# design_1.net
KiCad netlist of a schematic drawn in Altium Designer
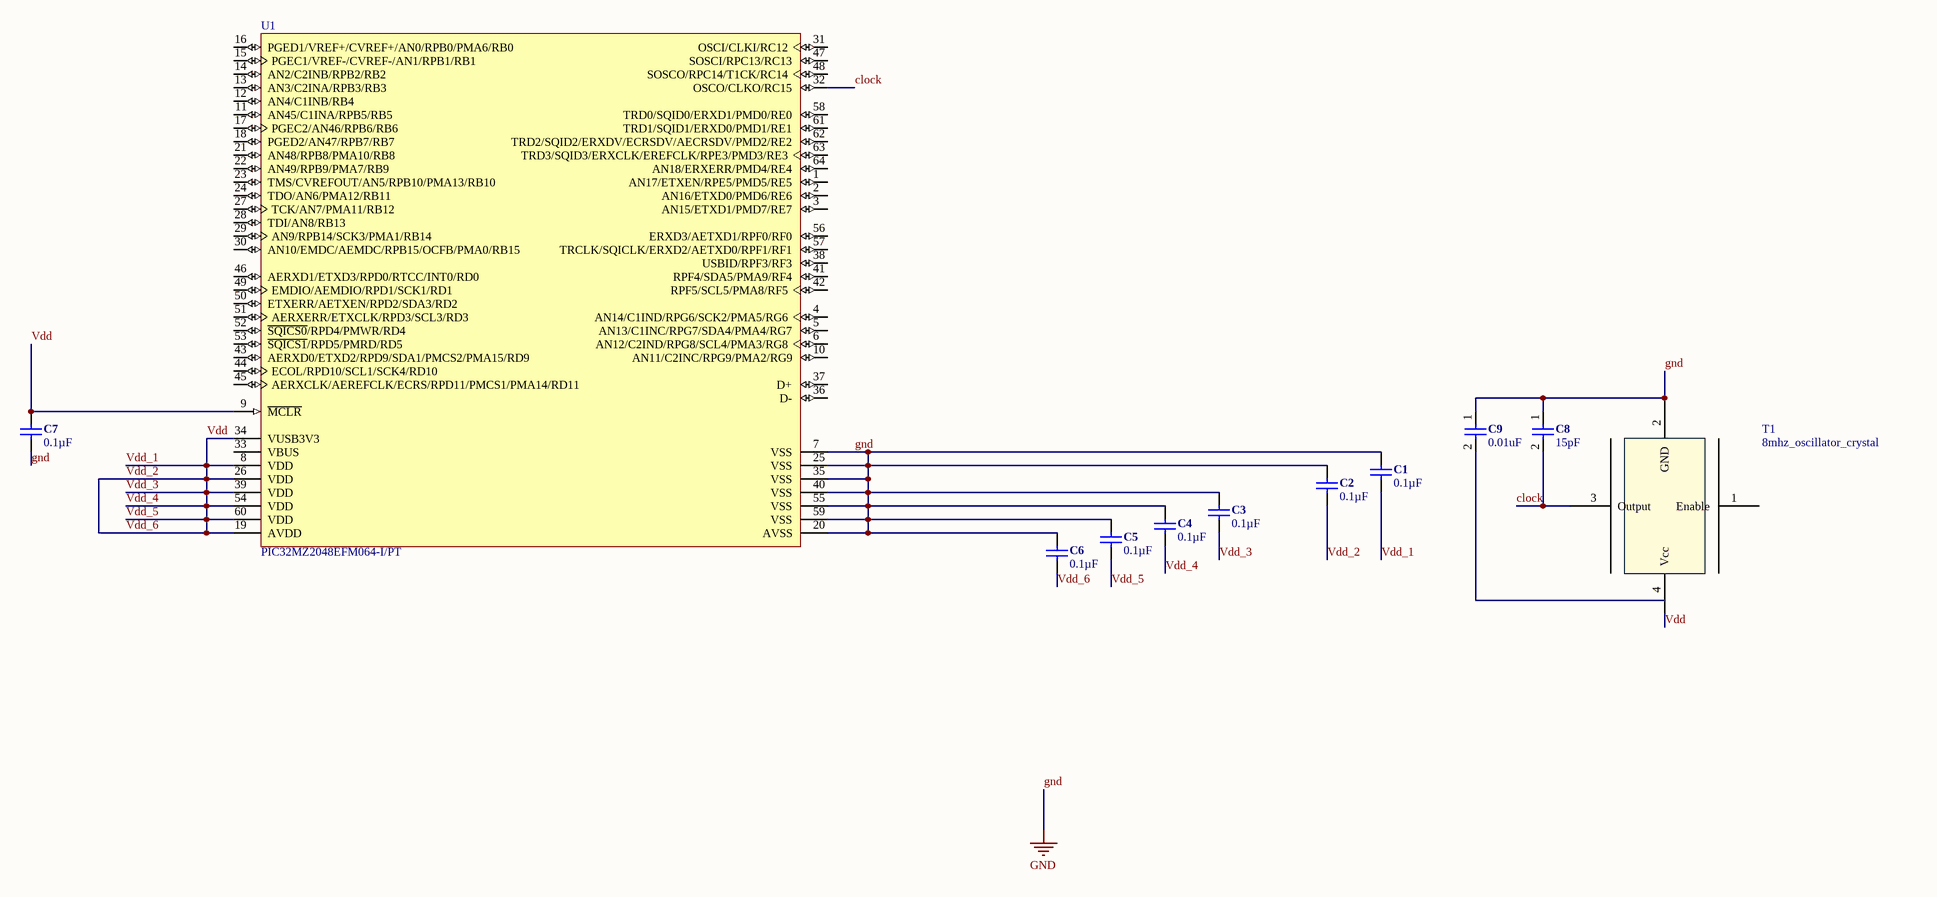
[diagram p0: design_1.SchDoc]

(export (version "E")
  (design (tool "Eeschema 10.0.6"))
  (components
    (comp (ref "C1")
      (value "0.1µF")
      (footprint "CAP-0402(1005)-R")
      (description "CAP CER 0.1UF 16V 10% X7R 0402")
      (fields (field (name "TOLERANCE") "±10%") (field (name "MANUFACTURER") "YAGEO"))
      (libsource (lib "MasterLibrary") (part "CAP-0.1uF-16V-CER-0402(1005)"))
    )
    (comp (ref "C2")
      (value "0.1µF")
      (footprint "CAP-0402(1005)-R")
      (description "CAP CER 0.1UF 16V 10% X7R 0402")
      (fields (field (name "TOLERANCE") "±10%") (field (name "MANUFACTURER") "YAGEO"))
      (libsource (lib "MasterLibrary") (part "CAP-0.1uF-16V-CER-0402(1005)"))
    )
    (comp (ref "C3")
      (value "0.1µF")
      (footprint "CAP-0402(1005)-R")
      (description "CAP CER 0.1UF 16V 10% X7R 0402")
      (fields (field (name "TOLERANCE") "±10%") (field (name "MANUFACTURER") "YAGEO"))
      (libsource (lib "MasterLibrary") (part "CAP-0.1uF-16V-CER-0402(1005)"))
    )
    (comp (ref "C4")
      (value "0.1µF")
      (footprint "CAP-0402(1005)-R")
      (description "CAP CER 0.1UF 16V 10% X7R 0402")
      (fields (field (name "TOLERANCE") "±10%") (field (name "MANUFACTURER") "YAGEO"))
      (libsource (lib "MasterLibrary") (part "CAP-0.1uF-16V-CER-0402(1005)"))
    )
    (comp (ref "C5")
      (value "0.1µF")
      (footprint "CAP-0402(1005)-R")
      (description "CAP CER 0.1UF 16V 10% X7R 0402")
      (fields (field (name "TOLERANCE") "±10%") (field (name "MANUFACTURER") "YAGEO"))
      (libsource (lib "MasterLibrary") (part "CAP-0.1uF-16V-CER-0402(1005)"))
    )
    (comp (ref "C6")
      (value "0.1µF")
      (footprint "CAP-0402(1005)-R")
      (description "CAP CER 0.1UF 16V 10% X7R 0402")
      (fields (field (name "TOLERANCE") "±10%") (field (name "MANUFACTURER") "YAGEO"))
      (libsource (lib "MasterLibrary") (part "CAP-0.1uF-16V-CER-0402(1005)"))
    )
    (comp (ref "C7")
      (value "0.1µF")
      (footprint "CAP-0402(1005)-R")
      (description "CAP CER 0.1UF 16V 10% X7R 0402")
      (fields (field (name "TOLERANCE") "±10%") (field (name "MANUFACTURER") "YAGEO"))
      (libsource (lib "MasterLibrary") (part "CAP-0.1uF-16V-CER-0402(1005)"))
    )
    (comp (ref "C8")
      (value "15pF")
      (footprint "CAP-15pF-25V-CER-0201(0603)")
      (description "CAP CER 15pF 25V 5% C0G 0603 Murata")
      (fields (field (name "TOLERANCE") "±5%"))
      (libsource (lib "MasaLibrary") (part "CAP-15pF-25V-CER-0201(0603)"))
    )
    (comp (ref "C9")
      (value "0.01uF")
      (footprint "CAP-0.01uF-25V-CER-0402(0603)")
      (description "CAP CER 0.01uF 25V 5% C0G 0402 yagoe")
      (fields (field (name "TOLERANCE") "±5%"))
      (libsource (lib "MasaLibrary") (part "CAP-0.01uF-25V-CER-0402(1005)"))
    )
    (comp (ref "T1")
      (value "8mhz_oscillator_crystal")
      (libsource (lib "MasterLibrary") (part "8mhz_oscillator_crystal"))
    )
    (comp (ref "U1")
      (value "PIC32MZ2048EFM064-I/PT")
      (footprint "TQFP-64")
      (fields (field (name "PARTNUMBER") "PIC32MZ1024ECG064-E/PT") (field (name "MANUFACTURER") "Microchip"))
      (libsource (lib "MasterLibrary") (part "PIC32MZ2048"))
    )
  )
  (nets
    (net (code "1") (name "/Vdd") (class "Default")
      (node (ref "C1") (pin "2") (pinfunction "2_2") (pintype "passive"))
      (node (ref "C2") (pin "2") (pinfunction "2_2") (pintype "passive"))
      (node (ref "C3") (pin "2") (pinfunction "2_2") (pintype "passive"))
      (node (ref "C4") (pin "2") (pinfunction "2_2") (pintype "passive"))
      (node (ref "C5") (pin "2") (pinfunction "2_2") (pintype "passive"))
      (node (ref "C6") (pin "2") (pinfunction "2_2") (pintype "passive"))
      (node (ref "C7") (pin "1") (pinfunction "1_1") (pintype "passive"))
      (node (ref "T1") (pin "4") (pinfunction "Vcc_4") (pintype "passive"))
      (node (ref "U1") (pin "19") (pinfunction "AVDD_19") (pintype "power_in"))
      (node (ref "U1") (pin "26") (pinfunction "VDD_26") (pintype "power_in"))
      (node (ref "U1") (pin "34") (pinfunction "VUSB3V3_34") (pintype "power_in"))
      (node (ref "U1") (pin "39") (pinfunction "VDD_39") (pintype "power_in"))
      (node (ref "U1") (pin "54") (pinfunction "VDD_54") (pintype "power_in"))
      (node (ref "U1") (pin "60") (pinfunction "VDD_60") (pintype "power_in"))
      (node (ref "U1") (pin "8") (pinfunction "VDD_8") (pintype "power_in"))
      (node (ref "U1") (pin "9") (pinfunction "~{MCLR}_9") (pintype "input"))
    )
    (net (code "2") (name "/clock") (class "Default")
      (node (ref "C8") (pin "2") (pinfunction "2_2") (pintype "passive"))
      (node (ref "T1") (pin "3") (pinfunction "Output_3") (pintype "passive"))
      (node (ref "U1") (pin "32") (pinfunction "OSCO/CLKO/RC15_32") (pintype "bidirectional"))
    )
    (net (code "3") (name "GND") (class "Default")
      (node (ref "C1") (pin "1") (pinfunction "1_1") (pintype "passive"))
      (node (ref "C2") (pin "1") (pinfunction "1_1") (pintype "passive"))
      (node (ref "C3") (pin "1") (pinfunction "1_1") (pintype "passive"))
      (node (ref "C4") (pin "1") (pinfunction "1_1") (pintype "passive"))
      (node (ref "C5") (pin "1") (pinfunction "1_1") (pintype "passive"))
      (node (ref "C6") (pin "1") (pinfunction "1_1") (pintype "passive"))
      (node (ref "C7") (pin "2") (pinfunction "2_2") (pintype "passive"))
      (node (ref "C8") (pin "1") (pinfunction "1_1") (pintype "passive"))
      (node (ref "C9") (pin "1") (pinfunction "1_1") (pintype "passive"))
      (node (ref "T1") (pin "2") (pinfunction "GND_2") (pintype "passive"))
      (node (ref "U1") (pin "20") (pinfunction "AVSS_20") (pintype "power_in"))
      (node (ref "U1") (pin "25") (pinfunction "VSS_25") (pintype "power_in"))
      (node (ref "U1") (pin "35") (pinfunction "VSS_35") (pintype "power_in"))
      (node (ref "U1") (pin "40") (pinfunction "VSS_40") (pintype "power_in"))
      (node (ref "U1") (pin "55") (pinfunction "VSS_55") (pintype "power_in"))
      (node (ref "U1") (pin "59") (pinfunction "VSS_59") (pintype "power_in"))
      (node (ref "U1") (pin "7") (pinfunction "VSS_7") (pintype "power_in"))
    )
    (net (code "4") (name "unconnected-(C9-Pad2)") (class "Default")
      (node (ref "C9") (pin "2") (pinfunction "2_2") (pintype "passive"))
    )
    (net (code "5") (name "unconnected-(T1-Enable-Pad1)") (class "Default")
      (node (ref "T1") (pin "1") (pinfunction "Enable_1") (pintype "passive"))
    )
    (net (code "6") (name "unconnected-(U1-AERXCLK{slash}AEREFCLK{slash}ECRS{slash}RPD11{slash}PMCS1{slash}PMA14{slash}RD11-Pad45)") (class "Default")
      (node (ref "U1") (pin "45") (pinfunction "AERXCLK/AEREFCLK/ECRS/RPD11/PMCS1/PMA14/RD11_45") (pintype "bidirectional"))
    )
    (net (code "7") (name "unconnected-(U1-AERXD0{slash}ETXD2{slash}RPD9{slash}SDA1{slash}PMCS2{slash}PMA15{slash}RD9-Pad43)") (class "Default")
      (node (ref "U1") (pin "43") (pinfunction "AERXD0/ETXD2/RPD9/SDA1/PMCS2/PMA15/RD9_43") (pintype "bidirectional"))
    )
    (net (code "8") (name "unconnected-(U1-AERXD1{slash}ETXD3{slash}RPD0{slash}RTCC{slash}INT0{slash}RD0-Pad46)") (class "Default")
      (node (ref "U1") (pin "46") (pinfunction "AERXD1/ETXD3/RPD0/RTCC/INT0/RD0_46") (pintype "bidirectional"))
    )
    (net (code "9") (name "unconnected-(U1-AERXERR{slash}ETXCLK{slash}RPD3{slash}SCL3{slash}RD3-Pad51)") (class "Default")
      (node (ref "U1") (pin "51") (pinfunction "AERXERR/ETXCLK/RPD3/SCL3/RD3_51") (pintype "bidirectional"))
    )
    (net (code "10") (name "unconnected-(U1-AN2{slash}C2INB{slash}RPB2{slash}RB2-Pad14)") (class "Default")
      (node (ref "U1") (pin "14") (pinfunction "AN2/C2INB/RPB2/RB2_14") (pintype "bidirectional"))
    )
    (net (code "11") (name "unconnected-(U1-AN3{slash}C2INA{slash}RPB3{slash}RB3-Pad13)") (class "Default")
      (node (ref "U1") (pin "13") (pinfunction "AN3/C2INA/RPB3/RB3_13") (pintype "bidirectional"))
    )
    (net (code "12") (name "unconnected-(U1-AN4{slash}C1INB{slash}RB4-Pad12)") (class "Default")
      (node (ref "U1") (pin "12") (pinfunction "AN4/C1INB/RB4_12") (pintype "bidirectional"))
    )
    (net (code "13") (name "unconnected-(U1-AN9{slash}RPB14{slash}SCK3{slash}PMA1{slash}RB14-Pad29)") (class "Default")
      (node (ref "U1") (pin "29") (pinfunction "AN9/RPB14/SCK3/PMA1/RB14_29") (pintype "bidirectional"))
    )
    (net (code "14") (name "unconnected-(U1-AN10{slash}EMDC{slash}AEMDC{slash}RPB15{slash}OCFB{slash}PMA0{slash}RB15-Pad30)") (class "Default")
      (node (ref "U1") (pin "30") (pinfunction "AN10/EMDC/AEMDC/RPB15/OCFB/PMA0/RB15_30") (pintype "bidirectional"))
    )
    (net (code "15") (name "unconnected-(U1-AN11{slash}C2INC{slash}RPG9{slash}PMA2{slash}RG9-Pad10)") (class "Default")
      (node (ref "U1") (pin "10") (pinfunction "AN11/C2INC/RPG9/PMA2/RG9_10") (pintype "bidirectional"))
    )
    (net (code "16") (name "unconnected-(U1-AN12{slash}C2IND{slash}RPG8{slash}SCL4{slash}PMA3{slash}RG8-Pad6)") (class "Default")
      (node (ref "U1") (pin "6") (pinfunction "AN12/C2IND/RPG8/SCL4/PMA3/RG8_6") (pintype "bidirectional"))
    )
    (net (code "17") (name "unconnected-(U1-AN13{slash}C1INC{slash}RPG7{slash}SDA4{slash}PMA4{slash}RG7-Pad5)") (class "Default")
      (node (ref "U1") (pin "5") (pinfunction "AN13/C1INC/RPG7/SDA4/PMA4/RG7_5") (pintype "bidirectional"))
    )
    (net (code "18") (name "unconnected-(U1-AN14{slash}C1IND{slash}RPG6{slash}SCK2{slash}PMA5{slash}RG6-Pad4)") (class "Default")
      (node (ref "U1") (pin "4") (pinfunction "AN14/C1IND/RPG6/SCK2/PMA5/RG6_4") (pintype "bidirectional"))
    )
    (net (code "19") (name "unconnected-(U1-AN15{slash}ETXD1{slash}PMD7{slash}RE7-Pad3)") (class "Default")
      (node (ref "U1") (pin "3") (pinfunction "AN15/ETXD1/PMD7/RE7_3") (pintype "bidirectional"))
    )
    (net (code "20") (name "unconnected-(U1-AN16{slash}ETXD0{slash}PMD6{slash}RE6-Pad2)") (class "Default")
      (node (ref "U1") (pin "2") (pinfunction "AN16/ETXD0/PMD6/RE6_2") (pintype "bidirectional"))
    )
    (net (code "21") (name "unconnected-(U1-AN17{slash}ETXEN{slash}RPE5{slash}PMD5{slash}RE5-Pad1)") (class "Default")
      (node (ref "U1") (pin "1") (pinfunction "AN17/ETXEN/RPE5/PMD5/RE5_1") (pintype "bidirectional"))
    )
    (net (code "22") (name "unconnected-(U1-AN18{slash}ERXERR{slash}PMD4{slash}RE4-Pad64)") (class "Default")
      (node (ref "U1") (pin "64") (pinfunction "AN18/ERXERR/PMD4/RE4_64") (pintype "bidirectional"))
    )
    (net (code "23") (name "unconnected-(U1-AN45{slash}C1INA{slash}RPB5{slash}RB5-Pad11)") (class "Default")
      (node (ref "U1") (pin "11") (pinfunction "AN45/C1INA/RPB5/RB5_11") (pintype "bidirectional"))
    )
    (net (code "24") (name "unconnected-(U1-AN48{slash}RPB8{slash}PMA10{slash}RB8-Pad21)") (class "Default")
      (node (ref "U1") (pin "21") (pinfunction "AN48/RPB8/PMA10/RB8_21") (pintype "bidirectional"))
    )
    (net (code "25") (name "unconnected-(U1-AN49{slash}RPB9{slash}PMA7{slash}RB9-Pad22)") (class "Default")
      (node (ref "U1") (pin "22") (pinfunction "AN49/RPB9/PMA7/RB9_22") (pintype "bidirectional"))
    )
    (net (code "26") (name "unconnected-(U1-D+-Pad37)") (class "Default")
      (node (ref "U1") (pin "37") (pinfunction "D+_37") (pintype "bidirectional"))
    )
    (net (code "27") (name "unconnected-(U1-D--Pad36)") (class "Default")
      (node (ref "U1") (pin "36") (pinfunction "D-_36") (pintype "bidirectional"))
    )
    (net (code "28") (name "unconnected-(U1-ECOL{slash}RPD10{slash}SCL1{slash}SCK4{slash}RD10-Pad44)") (class "Default")
      (node (ref "U1") (pin "44") (pinfunction "ECOL/RPD10/SCL1/SCK4/RD10_44") (pintype "bidirectional"))
    )
    (net (code "29") (name "unconnected-(U1-EMDIO{slash}AEMDIO{slash}RPD1{slash}SCK1{slash}RD1-Pad49)") (class "Default")
      (node (ref "U1") (pin "49") (pinfunction "EMDIO/AEMDIO/RPD1/SCK1/RD1_49") (pintype "bidirectional"))
    )
    (net (code "30") (name "unconnected-(U1-ERXD3{slash}AETXD1{slash}RPF0{slash}RF0-Pad56)") (class "Default")
      (node (ref "U1") (pin "56") (pinfunction "ERXD3/AETXD1/RPF0/RF0_56") (pintype "bidirectional"))
    )
    (net (code "31") (name "unconnected-(U1-ETXERR{slash}AETXEN{slash}RPD2{slash}SDA3{slash}RD2-Pad50)") (class "Default")
      (node (ref "U1") (pin "50") (pinfunction "ETXERR/AETXEN/RPD2/SDA3/RD2_50") (pintype "bidirectional"))
    )
    (net (code "32") (name "unconnected-(U1-OSCI{slash}CLKI{slash}RC12-Pad31)") (class "Default")
      (node (ref "U1") (pin "31") (pinfunction "OSCI/CLKI/RC12_31") (pintype "bidirectional"))
    )
    (net (code "33") (name "unconnected-(U1-PGEC1{slash}VREF-{slash}CVREF-{slash}AN1{slash}RPB1{slash}RB1-Pad15)") (class "Default")
      (node (ref "U1") (pin "15") (pinfunction "PGEC1/VREF-/CVREF-/AN1/RPB1/RB1_15") (pintype "bidirectional"))
    )
    (net (code "34") (name "unconnected-(U1-PGEC2{slash}AN46{slash}RPB6{slash}RB6-Pad17)") (class "Default")
      (node (ref "U1") (pin "17") (pinfunction "PGEC2/AN46/RPB6/RB6_17") (pintype "bidirectional"))
    )
    (net (code "35") (name "unconnected-(U1-PGED1{slash}VREF+{slash}CVREF+{slash}AN0{slash}RPB0{slash}PMA6{slash}RB0-Pad16)") (class "Default")
      (node (ref "U1") (pin "16") (pinfunction "PGED1/VREF+/CVREF+/AN0/RPB0/PMA6/RB0_16") (pintype "bidirectional"))
    )
    (net (code "36") (name "unconnected-(U1-PGED2{slash}AN47{slash}RPB7{slash}RB7-Pad18)") (class "Default")
      (node (ref "U1") (pin "18") (pinfunction "PGED2/AN47/RPB7/RB7_18") (pintype "bidirectional"))
    )
    (net (code "37") (name "unconnected-(U1-RPF4{slash}SDA5{slash}PMA9{slash}RF4-Pad41)") (class "Default")
      (node (ref "U1") (pin "41") (pinfunction "RPF4/SDA5/PMA9/RF4_41") (pintype "bidirectional"))
    )
    (net (code "38") (name "unconnected-(U1-RPF5{slash}SCL5{slash}PMA8{slash}RF5-Pad42)") (class "Default")
      (node (ref "U1") (pin "42") (pinfunction "RPF5/SCL5/PMA8/RF5_42") (pintype "bidirectional"))
    )
    (net (code "39") (name "unconnected-(U1-SOSCI{slash}RPC13{slash}RC13-Pad47)") (class "Default")
      (node (ref "U1") (pin "47") (pinfunction "SOSCI/RPC13/RC13_47") (pintype "bidirectional"))
    )
    (net (code "40") (name "unconnected-(U1-SOSCO{slash}RPC14{slash}T1CK{slash}RC14-Pad48)") (class "Default")
      (node (ref "U1") (pin "48") (pinfunction "SOSCO/RPC14/T1CK/RC14_48") (pintype "bidirectional"))
    )
    (net (code "41") (name "unconnected-(U1-TCK{slash}AN7{slash}PMA11{slash}RB12-Pad27)") (class "Default")
      (node (ref "U1") (pin "27") (pinfunction "TCK/AN7/PMA11/RB12_27") (pintype "bidirectional"))
    )
    (net (code "42") (name "unconnected-(U1-TDI{slash}AN8{slash}RB13-Pad28)") (class "Default")
      (node (ref "U1") (pin "28") (pinfunction "TDI/AN8/RB13_28") (pintype "bidirectional"))
    )
    (net (code "43") (name "unconnected-(U1-TDO{slash}AN6{slash}PMA12{slash}RB11-Pad24)") (class "Default")
      (node (ref "U1") (pin "24") (pinfunction "TDO/AN6/PMA12/RB11_24") (pintype "bidirectional"))
    )
    (net (code "44") (name "unconnected-(U1-TMS{slash}CVREFOUT{slash}AN5{slash}RPB10{slash}PMA13{slash}RB10-Pad23)") (class "Default")
      (node (ref "U1") (pin "23") (pinfunction "TMS/CVREFOUT/AN5/RPB10/PMA13/RB10_23") (pintype "bidirectional"))
    )
    (net (code "45") (name "unconnected-(U1-TRCLK{slash}SQICLK{slash}ERXD2{slash}AETXD0{slash}RPF1{slash}RF1-Pad57)") (class "Default")
      (node (ref "U1") (pin "57") (pinfunction "TRCLK/SQICLK/ERXD2/AETXD0/RPF1/RF1_57") (pintype "bidirectional"))
    )
    (net (code "46") (name "unconnected-(U1-TRD0{slash}SQID0{slash}ERXD1{slash}PMD0{slash}RE0-Pad58)") (class "Default")
      (node (ref "U1") (pin "58") (pinfunction "TRD0/SQID0/ERXD1/PMD0/RE0_58") (pintype "bidirectional"))
    )
    (net (code "47") (name "unconnected-(U1-TRD1{slash}SQID1{slash}ERXD0{slash}PMD1{slash}RE1-Pad61)") (class "Default")
      (node (ref "U1") (pin "61") (pinfunction "TRD1/SQID1/ERXD0/PMD1/RE1_61") (pintype "bidirectional"))
    )
    (net (code "48") (name "unconnected-(U1-TRD2{slash}SQID2{slash}ERXDV{slash}ECRSDV{slash}AECRSDV{slash}PMD2{slash}RE2-Pad62)") (class "Default")
      (node (ref "U1") (pin "62") (pinfunction "TRD2/SQID2/ERXDV/ECRSDV/AECRSDV/PMD2/RE2_62") (pintype "bidirectional"))
    )
    (net (code "49") (name "unconnected-(U1-TRD3{slash}SQID3{slash}ERXCLK{slash}EREFCLK{slash}RPE3{slash}PMD3{slash}RE3-Pad63)") (class "Default")
      (node (ref "U1") (pin "63") (pinfunction "TRD3/SQID3/ERXCLK/EREFCLK/RPE3/PMD3/RE3_63") (pintype "bidirectional"))
    )
    (net (code "50") (name "unconnected-(U1-USBID{slash}RPF3{slash}RF3-Pad38)") (class "Default")
      (node (ref "U1") (pin "38") (pinfunction "USBID/RPF3/RF3_38") (pintype "bidirectional"))
    )
    (net (code "51") (name "unconnected-(U1-VBUS-Pad33)") (class "Default")
      (node (ref "U1") (pin "33") (pinfunction "VBUS_33") (pintype "power_in"))
    )
    (net (code "52") (name "unconnected-(U1-~{SQICS0}{slash}RPD4{slash}PMWR{slash}RD4-Pad52)") (class "Default")
      (node (ref "U1") (pin "52") (pinfunction "~{SQICS0}/RPD4/PMWR/RD4_52") (pintype "bidirectional"))
    )
    (net (code "53") (name "unconnected-(U1-~{SQICS1}{slash}RPD5{slash}PMRD{slash}RD5-Pad53)") (class "Default")
      (node (ref "U1") (pin "53") (pinfunction "~{SQICS1}/RPD5/PMRD/RD5_53") (pintype "bidirectional"))
    )
  )
)
